# Power_Amp.net
KiCad netlist of a schematic drawn in Altium Designer
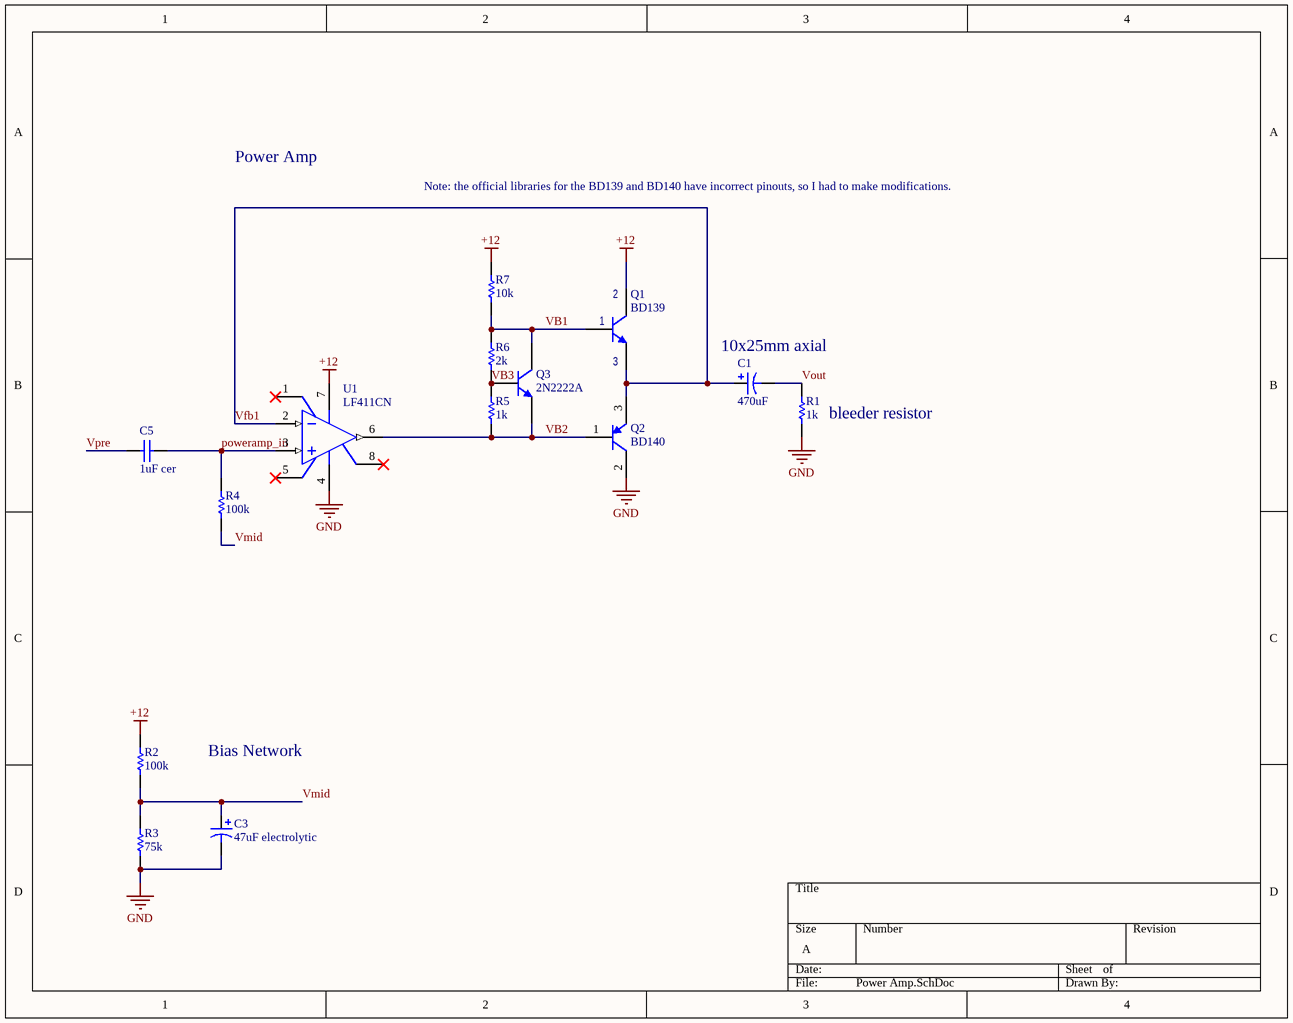
[diagram p0: Power Amp.SchDoc]

(export (version "E")
  (design (tool "Eeschema 10.0.6"))
  (components
    (comp (ref "C1")
      (value "470uF")
      (footprint "Capacitor")
      (description "Cap Aluminum 33uF 100V 20% (10 X 25mm) Axial 3.4 Ohm 140mA 4000h 125°C T/R")
      (libsource (lib "CommunityVault") (part "SYM-76c7be02e5fba900-1"))
    )
    (comp (ref "C3")
      (value "47uF electrolytic")
      (footprint "PCB-bs2nfpedd8vjo8odb39w-1")
      (description "Cap Aluminum Lytic 47uF 50V 20% (6.3 X 11.2mm) Radial 2.5mm 260mA 1000h 105C Automotive Bulk")
      (fields (field (name "MANUFACTURER PART NUMBER") "EEU-FC1H470"))
      (libsource (lib "Octopart library") (part "SYM-6ed4a5842ea2b113-1"))
    )
    (comp (ref "C5")
      (value "1uF cer")
      (footprint "PCB-19304320-1")
      (description "Capacitor; Ceramic; Cap 1.00uF; Tol 10%; Radial; Vol-Rtg 50V")
      (fields (field (name "MANUFACTURER PART NUMBER") "C330C105K5R5TA"))
      (libsource (lib "Octopart library") (part "SYM-bb267075e97664e1-1"))
    )
    (comp (ref "Q1")
      (value "BD139")
      (footprint "PCB-vxsgokorrilsux2zr6a3-1")
      (description "BD139 Series NPN 80 V 1.5 A Complementary Low Voltage Transistor - SOT-32")
      (libsource (lib "FavoritesLibrary") (part "SYM-919c5893dd954e5b-1"))
    )
    (comp (ref "Q2")
      (value "BD140")
      (footprint "ONSC-TO-225-3-77-09")
      (description "Plastic Medium-Power Silicon PNP Transistor, 3-Pin TO-225, Bulk Box")
      (libsource (lib "FavoritesLibrary") (part "ONSC-PNP-E1C2B3-3"))
    )
    (comp (ref "Q3")
      (value "2N2222A")
      (footprint "PCB-il5alzs33b9y8p1mx0ke-1")
      (description "Transistor, NPN, 40v, To-92")
      (libsource (lib "Octopart library") (part "SYM-e31e29598eb63cd9-1"))
    )
    (comp (ref "R1")
      (value "1k")
      (footprint "PCB-ufx52wqpb97u1085hkka-1")
      (description "Through Hole Carbon Film Resistor, CFR Series, 10 kohm, 500 mW, - 5%, 350 V, Axial Leaded")
      (libsource (lib "Octopart library") (part "SYM-0abbc281a318d57c-1"))
    )
    (comp (ref "R2")
      (value "100k")
      (footprint "PCB-ufx52wqpb97u1085hkka-1")
      (description "Through Hole Carbon Film Resistor, CFR Series, 10 kohm, 500 mW, - 5%, 350 V, Axial Leaded")
      (libsource (lib "Octopart library") (part "SYM-0abbc281a318d57c-1"))
    )
    (comp (ref "R3")
      (value "75k")
      (footprint "PCB-ufx52wqpb97u1085hkka-1")
      (description "Through Hole Carbon Film Resistor, CFR Series, 10 kohm, 500 mW, - 5%, 350 V, Axial Leaded")
      (libsource (lib "Octopart library") (part "SYM-0abbc281a318d57c-1"))
    )
    (comp (ref "R4")
      (value "100k")
      (footprint "PCB-ufx52wqpb97u1085hkka-1")
      (description "Through Hole Carbon Film Resistor, CFR Series, 10 kohm, 500 mW, - 5%, 350 V, Axial Leaded")
      (libsource (lib "Octopart library") (part "SYM-0abbc281a318d57c-1"))
    )
    (comp (ref "R5")
      (value "1k")
      (footprint "PCB-ufx52wqpb97u1085hkka-1")
      (description "Through Hole Carbon Film Resistor, CFR Series, 10 kohm, 500 mW, - 5%, 350 V, Axial Leaded")
      (libsource (lib "Octopart library") (part "SYM-0abbc281a318d57c-1"))
    )
    (comp (ref "R6")
      (value "2k")
      (footprint "PCB-ufx52wqpb97u1085hkka-1")
      (description "Through Hole Carbon Film Resistor, CFR Series, 10 kohm, 500 mW, - 5%, 350 V, Axial Leaded")
      (libsource (lib "Octopart library") (part "SYM-0abbc281a318d57c-1"))
    )
    (comp (ref "R7")
      (value "10k")
      (footprint "PCB-ufx52wqpb97u1085hkka-1")
      (description "Through Hole Carbon Film Resistor, CFR Series, 10 kohm, 500 mW, - 5%, 350 V, Axial Leaded")
      (libsource (lib "Octopart library") (part "SYM-0abbc281a318d57c-1"))
    )
    (comp (ref "U1")
      (value "LF411CN")
      (footprint "N08E")
      (description "Low Offset, Low Drift JFET Input Operational Amplifier, 8-pin MDIP")
      (libsource (lib "Octopart library") (part "AMP-OPA-LF156-8"))
    )
  )
  (nets
    (net (code "1") (name "+12") (class "Default")
      (node (ref "Q1") (pin "2") (pinfunction "C_2") (pintype "passive"))
      (node (ref "R2") (pin "2") (pinfunction "2_2") (pintype "passive"))
      (node (ref "R7") (pin "2") (pinfunction "2_2") (pintype "passive"))
      (node (ref "U1") (pin "7") (pinfunction "V+_7") (pintype "power_in"))
    )
    (net (code "2") (name "/VB1") (class "Default")
      (node (ref "Q1") (pin "1") (pinfunction "B_1") (pintype "passive"))
      (node (ref "Q3") (pin "3") (pinfunction "C_3") (pintype "passive"))
      (node (ref "R6") (pin "2") (pinfunction "2_2") (pintype "passive"))
      (node (ref "R7") (pin "1") (pinfunction "1_1") (pintype "passive"))
    )
    (net (code "3") (name "/VB2") (class "Default")
      (node (ref "Q2") (pin "1") (pinfunction "B_1") (pintype "passive"))
      (node (ref "Q3") (pin "1") (pinfunction "E_1") (pintype "passive"))
      (node (ref "R5") (pin "1") (pinfunction "1_1") (pintype "passive"))
      (node (ref "U1") (pin "6") (pinfunction "OUT_6") (pintype "output"))
    )
    (net (code "4") (name "/VB3") (class "Default")
      (node (ref "Q3") (pin "2") (pinfunction "B_2") (pintype "passive"))
      (node (ref "R5") (pin "2") (pinfunction "2_2") (pintype "passive"))
      (node (ref "R6") (pin "1") (pinfunction "1_1") (pintype "passive"))
    )
    (net (code "5") (name "/Vfb1") (class "Default")
      (node (ref "C1") (pin "1") (pinfunction "1_1") (pintype "passive"))
      (node (ref "Q1") (pin "3") (pinfunction "E_3") (pintype "passive"))
      (node (ref "Q2") (pin "3") (pinfunction "E_3") (pintype "passive"))
      (node (ref "U1") (pin "2") (pinfunction "IN-_2") (pintype "input"))
    )
    (net (code "6") (name "/Vmid") (class "Default")
      (node (ref "C3") (pin "1") (pinfunction "1_1") (pintype "passive"))
      (node (ref "R2") (pin "1") (pinfunction "1_1") (pintype "passive"))
      (node (ref "R3") (pin "2") (pinfunction "2_2") (pintype "passive"))
      (node (ref "R4") (pin "1") (pinfunction "1_1") (pintype "passive"))
    )
    (net (code "7") (name "/Vout") (class "Default")
      (node (ref "C1") (pin "2") (pinfunction "2_2") (pintype "passive"))
      (node (ref "R1") (pin "2") (pinfunction "2_2") (pintype "passive"))
    )
    (net (code "8") (name "/Vpre") (class "Default")
      (node (ref "C5") (pin "1") (pinfunction "1_1") (pintype "passive"))
    )
    (net (code "9") (name "/poweramp_in") (class "Default")
      (node (ref "C5") (pin "2") (pinfunction "2_2") (pintype "passive"))
      (node (ref "R4") (pin "2") (pinfunction "2_2") (pintype "passive"))
      (node (ref "U1") (pin "3") (pinfunction "IN+_3") (pintype "input"))
    )
    (net (code "10") (name "GND") (class "Default")
      (node (ref "C3") (pin "2") (pinfunction "2_2") (pintype "passive"))
      (node (ref "Q2") (pin "2") (pinfunction "C_2") (pintype "passive"))
      (node (ref "R1") (pin "1") (pinfunction "1_1") (pintype "passive"))
      (node (ref "R3") (pin "1") (pinfunction "1_1") (pintype "passive"))
      (node (ref "U1") (pin "4") (pinfunction "V-_4") (pintype "power_in"))
    )
    (net (code "11") (name "unconnected-(U1-BAL-Pad1)") (class "Default")
      (node (ref "U1") (pin "1") (pinfunction "BAL_1") (pintype "passive+no_connect"))
    )
    (net (code "12") (name "unconnected-(U1-BAL-Pad5)") (class "Default")
      (node (ref "U1") (pin "5") (pinfunction "BAL_5") (pintype "passive+no_connect"))
    )
    (net (code "13") (name "unconnected-(U1-NC-Pad8)") (class "Default")
      (node (ref "U1") (pin "8") (pinfunction "NC_8") (pintype "passive+no_connect"))
    )
  )
)
